# LedCube4x4x6OptoFin.net
KiCad netlist of a schematic drawn in EasyEDA
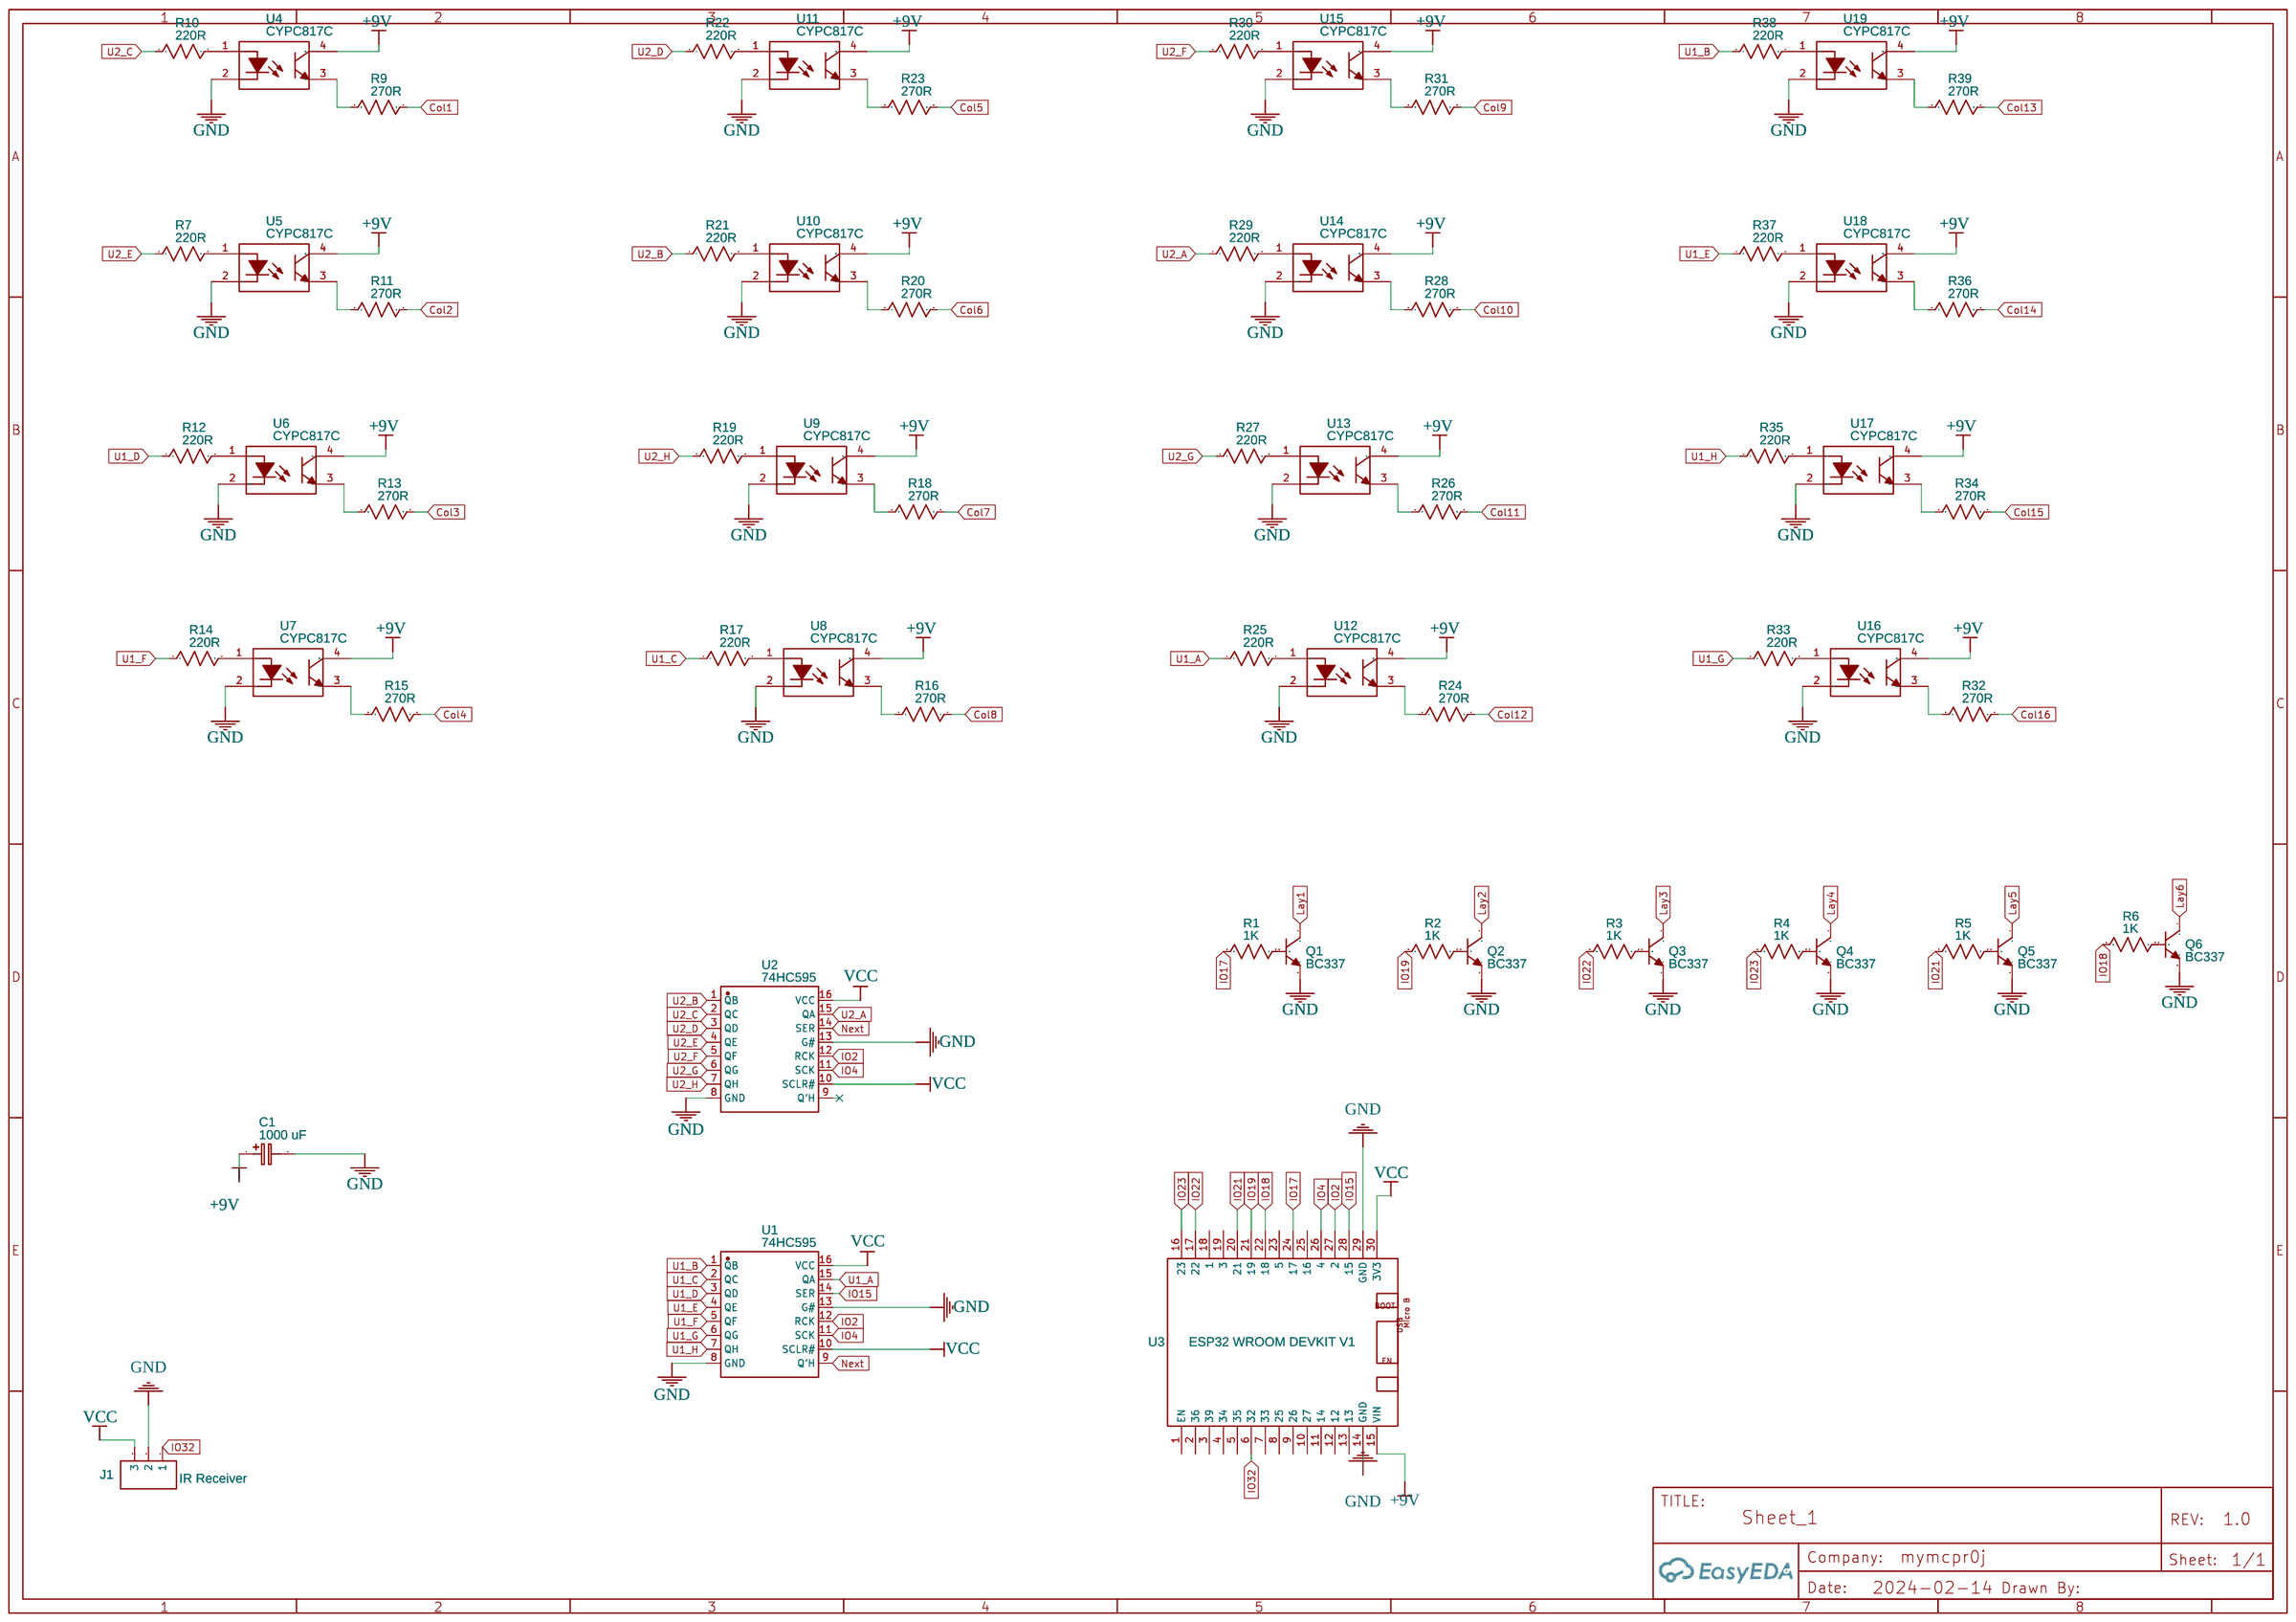
[diagram p0: schematic sheet]

(export (version "E")
  (design (tool "Eeschema 10.0.6"))
  (components
    (comp (ref "C1") (value "1000 uF") (libsource (lib "") (part "C_Tan_SMD_A_EU")))
    (comp (ref "J1") (value "IR Receiver") (libsource (lib "") (part "HDR-M-2.54_1x3")))
    (comp (ref "Q1")
      (value "BC337")
      (fields
        (field (name "Manufacturer Part") "2N2222A")
        (field (name "Manufacturer") "Foshan Blue Rocket Elec")
      )
      (libsource (lib "") (part "2N2222A"))
    )
    (comp (ref "Q2")
      (value "BC337")
      (fields
        (field (name "Manufacturer Part") "2N2222A")
        (field (name "Manufacturer") "Foshan Blue Rocket Elec")
      )
      (libsource (lib "") (part "2N2222A"))
    )
    (comp (ref "Q3")
      (value "BC337")
      (fields
        (field (name "Manufacturer Part") "2N2222A")
        (field (name "Manufacturer") "Foshan Blue Rocket Elec")
      )
      (libsource (lib "") (part "2N2222A"))
    )
    (comp (ref "Q4")
      (value "BC337")
      (fields
        (field (name "Manufacturer Part") "2N2222A")
        (field (name "Manufacturer") "Foshan Blue Rocket Elec")
      )
      (libsource (lib "") (part "2N2222A"))
    )
    (comp (ref "Q5")
      (value "BC337")
      (fields
        (field (name "Manufacturer Part") "2N2222A")
        (field (name "Manufacturer") "Foshan Blue Rocket Elec")
      )
      (libsource (lib "") (part "2N2222A"))
    )
    (comp (ref "Q6")
      (value "BC337")
      (fields
        (field (name "Manufacturer Part") "2N2222A")
        (field (name "Manufacturer") "Foshan Blue Rocket Elec")
      )
      (libsource (lib "") (part "2N2222A"))
    )
    (comp (ref "R1") (value "1K") (libsource (lib "") (part "R_0603_US_1")))
    (comp (ref "R2") (value "1K") (libsource (lib "") (part "R_0603_US_1")))
    (comp (ref "R3") (value "1K") (libsource (lib "") (part "R_0603_US_1")))
    (comp (ref "R4") (value "1K") (libsource (lib "") (part "R_0603_US_1")))
    (comp (ref "R5") (value "1K") (libsource (lib "") (part "R_0603_US_1")))
    (comp (ref "R6") (value "1K") (libsource (lib "") (part "R_0603_US_1")))
    (comp (ref "R7") (value "220R") (libsource (lib "") (part "R_0603_US")))
    (comp (ref "R9") (value "270R") (libsource (lib "") (part "R_0603_US")))
    (comp (ref "R10") (value "220R") (libsource (lib "") (part "R_0603_US")))
    (comp (ref "R11") (value "270R") (libsource (lib "") (part "R_0603_US")))
    (comp (ref "R12") (value "220R") (libsource (lib "") (part "R_0603_US")))
    (comp (ref "R13") (value "270R") (libsource (lib "") (part "R_0603_US")))
    (comp (ref "R14") (value "220R") (libsource (lib "") (part "R_0603_US")))
    (comp (ref "R15") (value "270R") (libsource (lib "") (part "R_0603_US")))
    (comp (ref "R16") (value "270R") (libsource (lib "") (part "R_0603_US")))
    (comp (ref "R17") (value "220R") (libsource (lib "") (part "R_0603_US")))
    (comp (ref "R18") (value "270R") (libsource (lib "") (part "R_0603_US")))
    (comp (ref "R19") (value "220R") (libsource (lib "") (part "R_0603_US")))
    (comp (ref "R20") (value "270R") (libsource (lib "") (part "R_0603_US")))
    (comp (ref "R21") (value "220R") (libsource (lib "") (part "R_0603_US")))
    (comp (ref "R22") (value "220R") (libsource (lib "") (part "R_0603_US")))
    (comp (ref "R23") (value "270R") (libsource (lib "") (part "R_0603_US")))
    (comp (ref "R24") (value "270R") (libsource (lib "") (part "R_0603_US")))
    (comp (ref "R25") (value "220R") (libsource (lib "") (part "R_0603_US")))
    (comp (ref "R26") (value "270R") (libsource (lib "") (part "R_0603_US")))
    (comp (ref "R27") (value "220R") (libsource (lib "") (part "R_0603_US")))
    (comp (ref "R28") (value "270R") (libsource (lib "") (part "R_0603_US")))
    (comp (ref "R29") (value "220R") (libsource (lib "") (part "R_0603_US")))
    (comp (ref "R30") (value "220R") (libsource (lib "") (part "R_0603_US")))
    (comp (ref "R31") (value "270R") (libsource (lib "") (part "R_0603_US")))
    (comp (ref "R32") (value "270R") (libsource (lib "") (part "R_0603_US")))
    (comp (ref "R33") (value "220R") (libsource (lib "") (part "R_0603_US")))
    (comp (ref "R34") (value "270R") (libsource (lib "") (part "R_0603_US")))
    (comp (ref "R35") (value "220R") (libsource (lib "") (part "R_0603_US")))
    (comp (ref "R36") (value "270R") (libsource (lib "") (part "R_0603_US")))
    (comp (ref "R37") (value "220R") (libsource (lib "") (part "R_0603_US")))
    (comp (ref "R38") (value "220R") (libsource (lib "") (part "R_0603_US")))
    (comp (ref "R39") (value "270R") (libsource (lib "") (part "R_0603_US")))
    (comp (ref "U1")
      (value "74HC595")
      (fields (field (name "Manufacturer") "GR(国睿)"))
      (libsource (lib "") (part "74HC595"))
    )
    (comp (ref "U2")
      (value "74HC595")
      (fields (field (name "Manufacturer") "GR(国睿)"))
      (libsource (lib "") (part "74HC595"))
    )
    (comp (ref "U3")
      (value "ESP32 WROOM DEVKIT V1")
      (libsource (lib "") (part "DOIT ESP32 DEVKIT ESP-WROOM-32 CP2102 WIFI Bluetooth ESP8266 w/ label"))
    )
    (comp (ref "U4")
      (value "CYPC817C")
      (fields (field (name "Manufacturer") "OCIC(卓睿科)"))
      (libsource (lib "") (part "CYPC817C"))
    )
    (comp (ref "U5")
      (value "CYPC817C")
      (fields (field (name "Manufacturer") "OCIC(卓睿科)"))
      (libsource (lib "") (part "CYPC817C"))
    )
    (comp (ref "U6")
      (value "CYPC817C")
      (fields (field (name "Manufacturer") "OCIC(卓睿科)"))
      (libsource (lib "") (part "CYPC817C"))
    )
    (comp (ref "U7")
      (value "CYPC817C")
      (fields (field (name "Manufacturer") "OCIC(卓睿科)"))
      (libsource (lib "") (part "CYPC817C"))
    )
    (comp (ref "U8")
      (value "CYPC817C")
      (fields (field (name "Manufacturer") "OCIC(卓睿科)"))
      (libsource (lib "") (part "CYPC817C"))
    )
    (comp (ref "U9")
      (value "CYPC817C")
      (fields (field (name "Manufacturer") "OCIC(卓睿科)"))
      (libsource (lib "") (part "CYPC817C"))
    )
    (comp (ref "U10")
      (value "CYPC817C")
      (fields (field (name "Manufacturer") "OCIC(卓睿科)"))
      (libsource (lib "") (part "CYPC817C"))
    )
    (comp (ref "U11")
      (value "CYPC817C")
      (fields (field (name "Manufacturer") "OCIC(卓睿科)"))
      (libsource (lib "") (part "CYPC817C"))
    )
    (comp (ref "U12")
      (value "CYPC817C")
      (fields (field (name "Manufacturer") "OCIC(卓睿科)"))
      (libsource (lib "") (part "CYPC817C"))
    )
    (comp (ref "U13")
      (value "CYPC817C")
      (fields (field (name "Manufacturer") "OCIC(卓睿科)"))
      (libsource (lib "") (part "CYPC817C"))
    )
    (comp (ref "U14")
      (value "CYPC817C")
      (fields (field (name "Manufacturer") "OCIC(卓睿科)"))
      (libsource (lib "") (part "CYPC817C"))
    )
    (comp (ref "U15")
      (value "CYPC817C")
      (fields (field (name "Manufacturer") "OCIC(卓睿科)"))
      (libsource (lib "") (part "CYPC817C"))
    )
    (comp (ref "U16")
      (value "CYPC817C")
      (fields (field (name "Manufacturer") "OCIC(卓睿科)"))
      (libsource (lib "") (part "CYPC817C"))
    )
    (comp (ref "U17")
      (value "CYPC817C")
      (fields (field (name "Manufacturer") "OCIC(卓睿科)"))
      (libsource (lib "") (part "CYPC817C"))
    )
    (comp (ref "U18")
      (value "CYPC817C")
      (fields (field (name "Manufacturer") "OCIC(卓睿科)"))
      (libsource (lib "") (part "CYPC817C"))
    )
    (comp (ref "U19")
      (value "CYPC817C")
      (fields (field (name "Manufacturer") "OCIC(卓睿科)"))
      (libsource (lib "") (part "CYPC817C"))
    )
  )
  (nets
    (net (code "1") (name "+9V") (class "Default")
      (node (ref "C1") (pin "1") (pinfunction "1_1") (pintype "unspecified"))
      (node (ref "U10") (pin "4") (pinfunction "COL_4") (pintype "unspecified"))
      (node (ref "U11") (pin "4") (pinfunction "COL_4") (pintype "unspecified"))
      (node (ref "U12") (pin "4") (pinfunction "COL_4") (pintype "unspecified"))
      (node (ref "U13") (pin "4") (pinfunction "COL_4") (pintype "unspecified"))
      (node (ref "U14") (pin "4") (pinfunction "COL_4") (pintype "unspecified"))
      (node (ref "U15") (pin "4") (pinfunction "COL_4") (pintype "unspecified"))
      (node (ref "U16") (pin "4") (pinfunction "COL_4") (pintype "unspecified"))
      (node (ref "U17") (pin "4") (pinfunction "COL_4") (pintype "unspecified"))
      (node (ref "U18") (pin "4") (pinfunction "COL_4") (pintype "unspecified"))
      (node (ref "U19") (pin "4") (pinfunction "COL_4") (pintype "unspecified"))
      (node (ref "U3") (pin "15") (pinfunction "VIN_15") (pintype "unspecified"))
      (node (ref "U4") (pin "4") (pinfunction "COL_4") (pintype "unspecified"))
      (node (ref "U5") (pin "4") (pinfunction "COL_4") (pintype "unspecified"))
      (node (ref "U6") (pin "4") (pinfunction "COL_4") (pintype "unspecified"))
      (node (ref "U7") (pin "4") (pinfunction "COL_4") (pintype "unspecified"))
      (node (ref "U8") (pin "4") (pinfunction "COL_4") (pintype "unspecified"))
      (node (ref "U9") (pin "4") (pinfunction "COL_4") (pintype "unspecified"))
    )
    (net (code "2") (name "Col1") (class "Default")
      (node (ref "R9") (pin "2") (pinfunction "2_2") (pintype "unspecified"))
    )
    (net (code "3") (name "Col2") (class "Default")
      (node (ref "R11") (pin "2") (pinfunction "2_2") (pintype "unspecified"))
    )
    (net (code "4") (name "Col3") (class "Default")
      (node (ref "R13") (pin "2") (pinfunction "2_2") (pintype "unspecified"))
    )
    (net (code "5") (name "Col4") (class "Default")
      (node (ref "R15") (pin "2") (pinfunction "2_2") (pintype "unspecified"))
    )
    (net (code "6") (name "Col5") (class "Default")
      (node (ref "R23") (pin "2") (pinfunction "2_2") (pintype "unspecified"))
    )
    (net (code "7") (name "Col6") (class "Default")
      (node (ref "R20") (pin "2") (pinfunction "2_2") (pintype "unspecified"))
    )
    (net (code "8") (name "Col7") (class "Default")
      (node (ref "R18") (pin "2") (pinfunction "2_2") (pintype "unspecified"))
    )
    (net (code "9") (name "Col8") (class "Default")
      (node (ref "R16") (pin "2") (pinfunction "2_2") (pintype "unspecified"))
    )
    (net (code "10") (name "Col9") (class "Default")
      (node (ref "R31") (pin "2") (pinfunction "2_2") (pintype "unspecified"))
    )
    (net (code "11") (name "Col10") (class "Default")
      (node (ref "R28") (pin "2") (pinfunction "2_2") (pintype "unspecified"))
    )
    (net (code "12") (name "Col11") (class "Default")
      (node (ref "R26") (pin "2") (pinfunction "2_2") (pintype "unspecified"))
    )
    (net (code "13") (name "Col12") (class "Default")
      (node (ref "R24") (pin "2") (pinfunction "2_2") (pintype "unspecified"))
    )
    (net (code "14") (name "Col13") (class "Default")
      (node (ref "R39") (pin "2") (pinfunction "2_2") (pintype "unspecified"))
    )
    (net (code "15") (name "Col14") (class "Default")
      (node (ref "R36") (pin "2") (pinfunction "2_2") (pintype "unspecified"))
    )
    (net (code "16") (name "Col15") (class "Default")
      (node (ref "R34") (pin "2") (pinfunction "2_2") (pintype "unspecified"))
    )
    (net (code "17") (name "Col16") (class "Default")
      (node (ref "R32") (pin "2") (pinfunction "2_2") (pintype "unspecified"))
    )
    (net (code "18") (name "GND") (class "Default")
      (node (ref "C1") (pin "2") (pinfunction "2_2") (pintype "unspecified"))
      (node (ref "J1") (pin "2") (pinfunction "2_2") (pintype "input"))
      (node (ref "Q1") (pin "3") (pinfunction "E_3") (pintype "unspecified"))
      (node (ref "Q2") (pin "3") (pinfunction "E_3") (pintype "unspecified"))
      (node (ref "Q3") (pin "3") (pinfunction "E_3") (pintype "unspecified"))
      (node (ref "Q4") (pin "3") (pinfunction "E_3") (pintype "unspecified"))
      (node (ref "Q5") (pin "3") (pinfunction "E_3") (pintype "unspecified"))
      (node (ref "Q6") (pin "3") (pinfunction "E_3") (pintype "unspecified"))
      (node (ref "U1") (pin "13") (pinfunction "G#_13") (pintype "unspecified"))
      (node (ref "U1") (pin "8") (pinfunction "GND_8") (pintype "unspecified"))
      (node (ref "U10") (pin "2") (pinfunction "CAT_2") (pintype "unspecified"))
      (node (ref "U11") (pin "2") (pinfunction "CAT_2") (pintype "unspecified"))
      (node (ref "U12") (pin "2") (pinfunction "CAT_2") (pintype "unspecified"))
      (node (ref "U13") (pin "2") (pinfunction "CAT_2") (pintype "unspecified"))
      (node (ref "U14") (pin "2") (pinfunction "CAT_2") (pintype "unspecified"))
      (node (ref "U15") (pin "2") (pinfunction "CAT_2") (pintype "unspecified"))
      (node (ref "U16") (pin "2") (pinfunction "CAT_2") (pintype "unspecified"))
      (node (ref "U17") (pin "2") (pinfunction "CAT_2") (pintype "unspecified"))
      (node (ref "U18") (pin "2") (pinfunction "CAT_2") (pintype "unspecified"))
      (node (ref "U19") (pin "2") (pinfunction "CAT_2") (pintype "unspecified"))
      (node (ref "U2") (pin "13") (pinfunction "G#_13") (pintype "unspecified"))
      (node (ref "U2") (pin "8") (pinfunction "GND_8") (pintype "unspecified"))
      (node (ref "U3") (pin "14") (pinfunction "GND_14") (pintype "unspecified"))
      (node (ref "U3") (pin "29") (pinfunction "GND_29") (pintype "unspecified"))
      (node (ref "U4") (pin "2") (pinfunction "CAT_2") (pintype "unspecified"))
      (node (ref "U5") (pin "2") (pinfunction "CAT_2") (pintype "unspecified"))
      (node (ref "U6") (pin "2") (pinfunction "CAT_2") (pintype "unspecified"))
      (node (ref "U7") (pin "2") (pinfunction "CAT_2") (pintype "unspecified"))
      (node (ref "U8") (pin "2") (pinfunction "CAT_2") (pintype "unspecified"))
      (node (ref "U9") (pin "2") (pinfunction "CAT_2") (pintype "unspecified"))
    )
    (net (code "19") (name "IO2") (class "Default")
      (node (ref "U1") (pin "12") (pinfunction "RCK_12") (pintype "unspecified"))
      (node (ref "U2") (pin "12") (pinfunction "RCK_12") (pintype "unspecified"))
      (node (ref "U3") (pin "27") (pinfunction "2_27") (pintype "unspecified"))
    )
    (net (code "20") (name "IO4") (class "Default")
      (node (ref "U1") (pin "11") (pinfunction "SCK_11") (pintype "unspecified"))
      (node (ref "U2") (pin "11") (pinfunction "SCK_11") (pintype "unspecified"))
      (node (ref "U3") (pin "26") (pinfunction "4_26") (pintype "unspecified"))
    )
    (net (code "21") (name "IO15") (class "Default")
      (node (ref "U1") (pin "14") (pinfunction "SER_14") (pintype "unspecified"))
      (node (ref "U3") (pin "28") (pinfunction "15_28") (pintype "unspecified"))
    )
    (net (code "22") (name "IO17") (class "Default")
      (node (ref "R1") (pin "2") (pinfunction "2_2") (pintype "unspecified"))
      (node (ref "U3") (pin "24") (pinfunction "17_24") (pintype "unspecified"))
    )
    (net (code "23") (name "IO18") (class "Default")
      (node (ref "R6") (pin "2") (pinfunction "2_2") (pintype "unspecified"))
      (node (ref "U3") (pin "22") (pinfunction "18_22") (pintype "unspecified"))
    )
    (net (code "24") (name "IO19") (class "Default")
      (node (ref "R2") (pin "2") (pinfunction "2_2") (pintype "unspecified"))
      (node (ref "U3") (pin "21") (pinfunction "19_21") (pintype "unspecified"))
    )
    (net (code "25") (name "IO21") (class "Default")
      (node (ref "R5") (pin "2") (pinfunction "2_2") (pintype "unspecified"))
      (node (ref "U3") (pin "20") (pinfunction "21_20") (pintype "unspecified"))
    )
    (net (code "26") (name "IO22") (class "Default")
      (node (ref "R3") (pin "2") (pinfunction "2_2") (pintype "unspecified"))
      (node (ref "U3") (pin "17") (pinfunction "22_17") (pintype "unspecified"))
    )
    (net (code "27") (name "IO23") (class "Default")
      (node (ref "R4") (pin "2") (pinfunction "2_2") (pintype "unspecified"))
      (node (ref "U3") (pin "16") (pinfunction "23_16") (pintype "unspecified"))
    )
    (net (code "28") (name "IO32") (class "Default")
      (node (ref "J1") (pin "1") (pinfunction "1_1") (pintype "input"))
      (node (ref "U3") (pin "6") (pinfunction "32_6") (pintype "unspecified"))
    )
    (net (code "29") (name "Lay1") (class "Default")
      (node (ref "Q1") (pin "1") (pinfunction "C_1") (pintype "unspecified"))
    )
    (net (code "30") (name "Lay2") (class "Default")
      (node (ref "Q2") (pin "1") (pinfunction "C_1") (pintype "unspecified"))
    )
    (net (code "31") (name "Lay3") (class "Default")
      (node (ref "Q3") (pin "1") (pinfunction "C_1") (pintype "unspecified"))
    )
    (net (code "32") (name "Lay4") (class "Default")
      (node (ref "Q4") (pin "1") (pinfunction "C_1") (pintype "unspecified"))
    )
    (net (code "33") (name "Lay5") (class "Default")
      (node (ref "Q5") (pin "1") (pinfunction "C_1") (pintype "unspecified"))
    )
    (net (code "34") (name "Lay6") (class "Default")
      (node (ref "Q6") (pin "1") (pinfunction "C_1") (pintype "unspecified"))
    )
    (net (code "35") (name "Net-(Q1-B)") (class "Default")
      (node (ref "Q1") (pin "2") (pinfunction "B_2") (pintype "unspecified"))
      (node (ref "R1") (pin "1") (pinfunction "1_1") (pintype "unspecified"))
    )
    (net (code "36") (name "Net-(Q2-B)") (class "Default")
      (node (ref "Q2") (pin "2") (pinfunction "B_2") (pintype "unspecified"))
      (node (ref "R2") (pin "1") (pinfunction "1_1") (pintype "unspecified"))
    )
    (net (code "37") (name "Net-(Q3-B)") (class "Default")
      (node (ref "Q3") (pin "2") (pinfunction "B_2") (pintype "unspecified"))
      (node (ref "R3") (pin "1") (pinfunction "1_1") (pintype "unspecified"))
    )
    (net (code "38") (name "Net-(Q4-B)") (class "Default")
      (node (ref "Q4") (pin "2") (pinfunction "B_2") (pintype "unspecified"))
      (node (ref "R4") (pin "1") (pinfunction "1_1") (pintype "unspecified"))
    )
    (net (code "39") (name "Net-(Q5-B)") (class "Default")
      (node (ref "Q5") (pin "2") (pinfunction "B_2") (pintype "unspecified"))
      (node (ref "R5") (pin "1") (pinfunction "1_1") (pintype "unspecified"))
    )
    (net (code "40") (name "Net-(Q6-B)") (class "Default")
      (node (ref "Q6") (pin "2") (pinfunction "B_2") (pintype "unspecified"))
      (node (ref "R6") (pin "1") (pinfunction "1_1") (pintype "unspecified"))
    )
    (net (code "41") (name "Net-(U4-AN)") (class "Default")
      (node (ref "R10") (pin "2") (pinfunction "2_2") (pintype "unspecified"))
      (node (ref "U4") (pin "1") (pinfunction "AN_1") (pintype "unspecified"))
    )
    (net (code "42") (name "Net-(U4-EMI)") (class "Default")
      (node (ref "R9") (pin "1") (pinfunction "1_1") (pintype "unspecified"))
      (node (ref "U4") (pin "3") (pinfunction "EMI_3") (pintype "unspecified"))
    )
    (net (code "43") (name "Net-(U5-AN)") (class "Default")
      (node (ref "R7") (pin "2") (pinfunction "2_2") (pintype "unspecified"))
      (node (ref "U5") (pin "1") (pinfunction "AN_1") (pintype "unspecified"))
    )
    (net (code "44") (name "Net-(U5-EMI)") (class "Default")
      (node (ref "R11") (pin "1") (pinfunction "1_1") (pintype "unspecified"))
      (node (ref "U5") (pin "3") (pinfunction "EMI_3") (pintype "unspecified"))
    )
    (net (code "45") (name "Net-(U6-AN)") (class "Default")
      (node (ref "R12") (pin "2") (pinfunction "2_2") (pintype "unspecified"))
      (node (ref "U6") (pin "1") (pinfunction "AN_1") (pintype "unspecified"))
    )
    (net (code "46") (name "Net-(U6-EMI)") (class "Default")
      (node (ref "R13") (pin "1") (pinfunction "1_1") (pintype "unspecified"))
      (node (ref "U6") (pin "3") (pinfunction "EMI_3") (pintype "unspecified"))
    )
    (net (code "47") (name "Net-(U7-AN)") (class "Default")
      (node (ref "R14") (pin "2") (pinfunction "2_2") (pintype "unspecified"))
      (node (ref "U7") (pin "1") (pinfunction "AN_1") (pintype "unspecified"))
    )
    (net (code "48") (name "Net-(U7-EMI)") (class "Default")
      (node (ref "R15") (pin "1") (pinfunction "1_1") (pintype "unspecified"))
      (node (ref "U7") (pin "3") (pinfunction "EMI_3") (pintype "unspecified"))
    )
    (net (code "49") (name "Net-(U8-AN)") (class "Default")
      (node (ref "R17") (pin "2") (pinfunction "2_2") (pintype "unspecified"))
      (node (ref "U8") (pin "1") (pinfunction "AN_1") (pintype "unspecified"))
    )
    (net (code "50") (name "Net-(U8-EMI)") (class "Default")
      (node (ref "R16") (pin "1") (pinfunction "1_1") (pintype "unspecified"))
      (node (ref "U8") (pin "3") (pinfunction "EMI_3") (pintype "unspecified"))
    )
    (net (code "51") (name "Net-(U9-AN)") (class "Default")
      (node (ref "R19") (pin "2") (pinfunction "2_2") (pintype "unspecified"))
      (node (ref "U9") (pin "1") (pinfunction "AN_1") (pintype "unspecified"))
    )
    (net (code "52") (name "Net-(U9-EMI)") (class "Default")
      (node (ref "R18") (pin "1") (pinfunction "1_1") (pintype "unspecified"))
      (node (ref "U9") (pin "3") (pinfunction "EMI_3") (pintype "unspecified"))
    )
    (net (code "53") (name "Net-(U10-AN)") (class "Default")
      (node (ref "R21") (pin "2") (pinfunction "2_2") (pintype "unspecified"))
      (node (ref "U10") (pin "1") (pinfunction "AN_1") (pintype "unspecified"))
    )
    (net (code "54") (name "Net-(U10-EMI)") (class "Default")
      (node (ref "R20") (pin "1") (pinfunction "1_1") (pintype "unspecified"))
      (node (ref "U10") (pin "3") (pinfunction "EMI_3") (pintype "unspecified"))
    )
    (net (code "55") (name "Net-(U11-AN)") (class "Default")
      (node (ref "R22") (pin "2") (pinfunction "2_2") (pintype "unspecified"))
      (node (ref "U11") (pin "1") (pinfunction "AN_1") (pintype "unspecified"))
    )
    (net (code "56") (name "Net-(U11-EMI)") (class "Default")
      (node (ref "R23") (pin "1") (pinfunction "1_1") (pintype "unspecified"))
      (node (ref "U11") (pin "3") (pinfunction "EMI_3") (pintype "unspecified"))
    )
    (net (code "57") (name "Net-(U12-AN)") (class "Default")
      (node (ref "R25") (pin "2") (pinfunction "2_2") (pintype "unspecified"))
      (node (ref "U12") (pin "1") (pinfunction "AN_1") (pintype "unspecified"))
    )
    (net (code "58") (name "Net-(U12-EMI)") (class "Default")
      (node (ref "R24") (pin "1") (pinfunction "1_1") (pintype "unspecified"))
      (node (ref "U12") (pin "3") (pinfunction "EMI_3") (pintype "unspecified"))
    )
    (net (code "59") (name "Net-(U13-AN)") (class "Default")
      (node (ref "R27") (pin "2") (pinfunction "2_2") (pintype "unspecified"))
      (node (ref "U13") (pin "1") (pinfunction "AN_1") (pintype "unspecified"))
    )
    (net (code "60") (name "Net-(U13-EMI)") (class "Default")
      (node (ref "R26") (pin "1") (pinfunction "1_1") (pintype "unspecified"))
      (node (ref "U13") (pin "3") (pinfunction "EMI_3") (pintype "unspecified"))
    )
    (net (code "61") (name "Net-(U14-AN)") (class "Default")
      (node (ref "R29") (pin "2") (pinfunction "2_2") (pintype "unspecified"))
      (node (ref "U14") (pin "1") (pinfunction "AN_1") (pintype "unspecified"))
    )
    (net (code "62") (name "Net-(U14-EMI)") (class "Default")
      (node (ref "R28") (pin "1") (pinfunction "1_1") (pintype "unspecified"))
      (node (ref "U14") (pin "3") (pinfunction "EMI_3") (pintype "unspecified"))
    )
    (net (code "63") (name "Net-(U15-AN)") (class "Default")
      (node (ref "R30") (pin "2") (pinfunction "2_2") (pintype "unspecified"))
      (node (ref "U15") (pin "1") (pinfunction "AN_1") (pintype "unspecified"))
    )
    (net (code "64") (name "Net-(U15-EMI)") (class "Default")
      (node (ref "R31") (pin "1") (pinfunction "1_1") (pintype "unspecified"))
      (node (ref "U15") (pin "3") (pinfunction "EMI_3") (pintype "unspecified"))
    )
    (net (code "65") (name "Net-(U16-AN)") (class "Default")
      (node (ref "R33") (pin "2") (pinfunction "2_2") (pintype "unspecified"))
      (node (ref "U16") (pin "1") (pinfunction "AN_1") (pintype "unspecified"))
    )
    (net (code "66") (name "Net-(U16-EMI)") (class "Default")
      (node (ref "R32") (pin "1") (pinfunction "1_1") (pintype "unspecified"))
      (node (ref "U16") (pin "3") (pinfunction "EMI_3") (pintype "unspecified"))
    )
    (net (code "67") (name "Net-(U17-AN)") (class "Default")
      (node (ref "R35") (pin "2") (pinfunction "2_2") (pintype "unspecified"))
      (node (ref "U17") (pin "1") (pinfunction "AN_1") (pintype "unspecified"))
    )
    (net (code "68") (name "Net-(U17-EMI)") (class "Default")
      (node (ref "R34") (pin "1") (pinfunction "1_1") (pintype "unspecified"))
      (node (ref "U17") (pin "3") (pinfunction "EMI_3") (pintype "unspecified"))
    )
    (net (code "69") (name "Net-(U18-AN)") (class "Default")
      (node (ref "R37") (pin "2") (pinfunction "2_2") (pintype "unspecified"))
      (node (ref "U18") (pin "1") (pinfunction "AN_1") (pintype "unspecified"))
    )
    (net (code "70") (name "Net-(U18-EMI)") (class "Default")
      (node (ref "R36") (pin "1") (pinfunction "1_1") (pintype "unspecified"))
      (node (ref "U18") (pin "3") (pinfunction "EMI_3") (pintype "unspecified"))
    )
    (net (code "71") (name "Net-(U19-AN)") (class "Default")
      (node (ref "R38") (pin "2") (pinfunction "2_2") (pintype "unspecified"))
      (node (ref "U19") (pin "1") (pinfunction "AN_1") (pintype "unspecified"))
    )
    (net (code "72") (name "Net-(U19-EMI)") (class "Default")
      (node (ref "R39") (pin "1") (pinfunction "1_1") (pintype "unspecified"))
      (node (ref "U19") (pin "3") (pinfunction "EMI_3") (pintype "unspecified"))
    )
    (net (code "73") (name "Next") (class "Default")
      (node (ref "U1") (pin "9") (pinfunction "Q′H_9") (pintype "unspecified"))
      (node (ref "U2") (pin "14") (pinfunction "SER_14") (pintype "unspecified"))
    )
    (net (code "74") (name "U1_A") (class "Default")
      (node (ref "R25") (pin "1") (pinfunction "1_1") (pintype "unspecified"))
      (node (ref "U1") (pin "15") (pinfunction "QA_15") (pintype "unspecified"))
    )
    (net (code "75") (name "U1_B") (class "Default")
      (node (ref "R38") (pin "1") (pinfunction "1_1") (pintype "unspecified"))
      (node (ref "U1") (pin "1") (pinfunction "QB_1") (pintype "unspecified"))
    )
    (net (code "76") (name "U1_C") (class "Default")
      (node (ref "R17") (pin "1") (pinfunction "1_1") (pintype "unspecified"))
      (node (ref "U1") (pin "2") (pinfunction "QC_2") (pintype "unspecified"))
    )
    (net (code "77") (name "U1_D") (class "Default")
      (node (ref "R12") (pin "1") (pinfunction "1_1") (pintype "unspecified"))
      (node (ref "U1") (pin "3") (pinfunction "QD_3") (pintype "unspecified"))
    )
    (net (code "78") (name "U1_E") (class "Default")
      (node (ref "R37") (pin "1") (pinfunction "1_1") (pintype "unspecified"))
      (node (ref "U1") (pin "4") (pinfunction "QE_4") (pintype "unspecified"))
    )
    (net (code "79") (name "U1_F") (class "Default")
      (node (ref "R14") (pin "1") (pinfunction "1_1") (pintype "unspecified"))
      (node (ref "U1") (pin "5") (pinfunction "QF_5") (pintype "unspecified"))
    )
    (net (code "80") (name "U1_G") (class "Default")
      (node (ref "R33") (pin "1") (pinfunction "1_1") (pintype "unspecified"))
      (node (ref "U1") (pin "6") (pinfunction "QG_6") (pintype "unspecified"))
    )
    (net (code "81") (name "U1_H") (class "Default")
      (node (ref "R35") (pin "1") (pinfunction "1_1") (pintype "unspecified"))
      (node (ref "U1") (pin "7") (pinfunction "QH_7") (pintype "unspecified"))
    )
    (net (code "82") (name "U2_A") (class "Default")
      (node (ref "R29") (pin "1") (pinfunction "1_1") (pintype "unspecified"))
      (node (ref "U2") (pin "15") (pinfunction "QA_15") (pintype "unspecified"))
    )
    (net (code "83") (name "U2_B") (class "Default")
      (node (ref "R21") (pin "1") (pinfunction "1_1") (pintype "unspecified"))
      (node (ref "U2") (pin "1") (pinfunction "QB_1") (pintype "unspecified"))
    )
    (net (code "84") (name "U2_C") (class "Default")
      (node (ref "R10") (pin "1") (pinfunction "1_1") (pintype "unspecified"))
      (node (ref "U2") (pin "2") (pinfunction "QC_2") (pintype "unspecified"))
    )
    (net (code "85") (name "U2_D") (class "Default")
      (node (ref "R22") (pin "1") (pinfunction "1_1") (pintype "unspecified"))
      (node (ref "U2") (pin "3") (pinfunction "QD_3") (pintype "unspecified"))
    )
    (net (code "86") (name "U2_E") (class "Default")
      (node (ref "R7") (pin "1") (pinfunction "1_1") (pintype "unspecified"))
      (node (ref "U2") (pin "4") (pinfunction "QE_4") (pintype "unspecified"))
    )
    (net (code "87") (name "U2_F") (class "Default")
      (node (ref "R30") (pin "1") (pinfunction "1_1") (pintype "unspecified"))
      (node (ref "U2") (pin "5") (pinfunction "QF_5") (pintype "unspecified"))
    )
    (net (code "88") (name "U2_G") (class "Default")
      (node (ref "R27") (pin "1") (pinfunction "1_1") (pintype "unspecified"))
      (node (ref "U2") (pin "6") (pinfunction "QG_6") (pintype "unspecified"))
    )
    (net (code "89") (name "U2_H") (class "Default")
      (node (ref "R19") (pin "1") (pinfunction "1_1") (pintype "unspecified"))
      (node (ref "U2") (pin "7") (pinfunction "QH_7") (pintype "unspecified"))
    )
    (net (code "90") (name "VCC") (class "Default")
      (node (ref "J1") (pin "3") (pinfunction "3_3") (pintype "input"))
      (node (ref "U1") (pin "10") (pinfunction "SCLR#_10") (pintype "unspecified"))
      (node (ref "U1") (pin "16") (pinfunction "VCC_16") (pintype "unspecified"))
      (node (ref "U2") (pin "10") (pinfunction "SCLR#_10") (pintype "unspecified"))
      (node (ref "U2") (pin "16") (pinfunction "VCC_16") (pintype "unspecified"))
      (node (ref "U3") (pin "30") (pinfunction "3V3_30") (pintype "unspecified"))
    )
    (net (code "91") (name "unconnected-(U2-Q′H-Pad9)") (class "Default")
      (node (ref "U2") (pin "9") (pinfunction "Q′H_9") (pintype "unspecified+no_connect"))
    )
    (net (code "92") (name "unconnected-(U3-1-Pad18)") (class "Default")
      (node (ref "U3") (pin "18") (pinfunction "1_18") (pintype "unspecified"))
    )
    (net (code "93") (name "unconnected-(U3-3-Pad19)") (class "Default")
      (node (ref "U3") (pin "19") (pinfunction "3_19") (pintype "unspecified"))
    )
    (net (code "94") (name "unconnected-(U3-5-Pad23)") (class "Default")
      (node (ref "U3") (pin "23") (pinfunction "5_23") (pintype "unspecified"))
    )
    (net (code "95") (name "unconnected-(U3-14-Pad11)") (class "Default")
      (node (ref "U3") (pin "11") (pinfunction "14_11") (pintype "unspecified"))
    )
    (net (code "96") (name "unconnected-(U3-16-Pad25)") (class "Default")
      (node (ref "U3") (pin "25") (pinfunction "16_25") (pintype "unspecified"))
    )
    (net (code "97") (name "unconnected-(U3-25-Pad8)") (class "Default")
      (node (ref "U3") (pin "8") (pinfunction "25_8") (pintype "unspecified"))
    )
    (net (code "98") (name "unconnected-(U3-26-Pad9)") (class "Default")
      (node (ref "U3") (pin "9") (pinfunction "26_9") (pintype "unspecified"))
    )
    (net (code "99") (name "unconnected-(U3-27-Pad10)") (class "Default")
      (node (ref "U3") (pin "10") (pinfunction "27_10") (pintype "unspecified"))
    )
    (net (code "100") (name "unconnected-(U3-33-Pad7)") (class "Default")
      (node (ref "U3") (pin "7") (pinfunction "33_7") (pintype "unspecified"))
    )
    (net (code "101") (name "unconnected-(U3-34-Pad4)") (class "Default")
      (node (ref "U3") (pin "4") (pinfunction "34_4") (pintype "unspecified"))
    )
    (net (code "102") (name "unconnected-(U3-35-Pad5)") (class "Default")
      (node (ref "U3") (pin "5") (pinfunction "35_5") (pintype "unspecified"))
    )
    (net (code "103") (name "unconnected-(U3-36-Pad2)") (class "Default")
      (node (ref "U3") (pin "2") (pinfunction "36_2") (pintype "unspecified"))
    )
    (net (code "104") (name "unconnected-(U3-39-Pad3)") (class "Default")
      (node (ref "U3") (pin "3") (pinfunction "39_3") (pintype "unspecified"))
    )
    (net (code "105") (name "unconnected-(U3-EN-Pad1)") (class "Default")
      (node (ref "U3") (pin "1") (pinfunction "EN_1") (pintype "unspecified"))
    )
    (net (code "106") (name "unconnected-(U3-Pad12)") (class "Default")
      (node (ref "U3") (pin "12") (pinfunction "12_12") (pintype "unspecified"))
    )
    (net (code "107") (name "unconnected-(U3-Pad13)") (class "Default")
      (node (ref "U3") (pin "13") (pinfunction "13_13") (pintype "unspecified"))
    )
  )
)
